# 01_MPPT_controller.net
KiCad netlist of a schematic drawn in Altium Designer
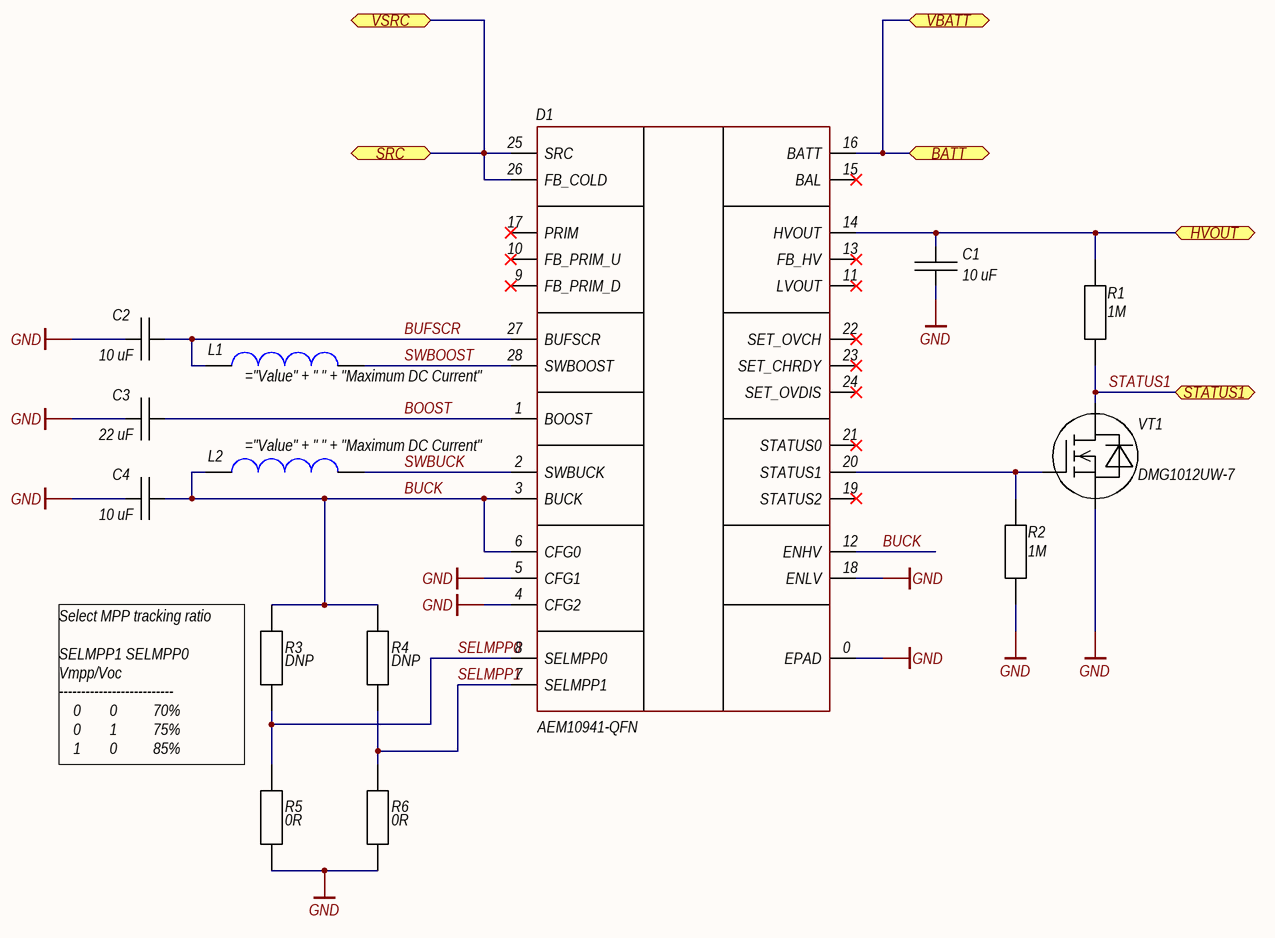
[diagram p0: 01_MPPT_controller.SchDoc]

(export (version "E")
  (design (tool "Eeschema 10.0.6"))
  (components
    (comp (ref "C1")
      (value "10 uF")
      (footprint "CAPC1608X09N")
      (description "Ceramic capacitor")
      (fields
        (field (name "MANUFACTURER") "Murata Electronics")
        (field (name "PARTNUMBER") "GRM188R61A106ME69D")
      )
      (libsource (lib "Node01") (part "Ceramic"))
    )
    (comp (ref "C2")
      (value "10 uF")
      (footprint "CAPC1608X09N")
      (description "Ceramic capacitor")
      (fields
        (field (name "MANUFACTURER") "Murata Electronics")
        (field (name "PARTNUMBER") "GRM188R61A106ME69D")
      )
      (libsource (lib "Node01") (part "Ceramic"))
    )
    (comp (ref "C3")
      (value "22 uF")
      (footprint "CAPC1608X09N")
      (description "Ceramic capacitor")
      (fields
        (field (name "MANUFACTURER") "Murata Electronics")
        (field (name "PARTNUMBER") "GRM188R61A226ME15D")
      )
      (libsource (lib "Node01") (part "Ceramic"))
    )
    (comp (ref "C4")
      (value "10 uF")
      (footprint "CAPC1608X09N")
      (description "Ceramic capacitor")
      (fields
        (field (name "MANUFACTURER") "Murata Electronics")
        (field (name "PARTNUMBER") "GRM188R61A106ME69D")
      )
      (libsource (lib "Node01") (part "Ceramic"))
    )
    (comp (ref "D1")
      (value "~")
      (footprint "QFN50P500X500X85_HS-29N")
      (fields (field (name "MANUFACTURER") "e-peas") (field (name "PARTNUMBER") "AEM10941-QFN"))
      (libsource (lib "Node01") (part "AEM10941-QFN28"))
    )
    (comp (ref "L1")
      (value "10 uH750 mA")
      (footprint "INDP3939X11N")
      (description "Inductor")
      (fields (field (name "MANUFACTURER") "Coilcraft") (field (name "PARTNUMBER") "LPS4012-103MRB"))
      (libsource (lib "Node01") (part "Inductor"))
    )
    (comp (ref "L2")
      (value "10 uH250 mA")
      (footprint "INDC1608X08N")
      (description "Inductor")
      (fields (field (name "MANUFACTURER") "TDK") (field (name "PARTNUMBER") "MLZ1608M100WT000"))
      (libsource (lib "Node01") (part "Inductor"))
    )
    (comp (ref "R1")
      (value "1M")
      (footprint "RESC1608X05N")
      (description "SMD resistor")
      (fields (field (name "MANUFACTURER") "Yageo") (field (name "PARTNUMBER") "RC0603JR-071ML"))
      (libsource (lib "Node01") (part "resistor_smd"))
    )
    (comp (ref "R2")
      (value "1M")
      (footprint "RESC1608X05N")
      (description "SMD resistor")
      (fields (field (name "MANUFACTURER") "Yageo") (field (name "PARTNUMBER") "RC0603JR-071ML"))
      (libsource (lib "Node01") (part "resistor_smd"))
    )
    (comp (ref "R3")
      (value "DNP")
      (footprint "RESC1608X05N")
      (description "SMD resistor")
      (fields (field (name "MANUFACTURER") "Yageo") (field (name "PARTNUMBER") "AC0603FR-070RL"))
      (libsource (lib "Node01") (part "resistor_smd"))
    )
    (comp (ref "R4")
      (value "DNP")
      (footprint "RESC1608X05N")
      (description "SMD resistor")
      (fields (field (name "MANUFACTURER") "Yageo") (field (name "PARTNUMBER") "AC0603FR-070RL"))
      (libsource (lib "Node01") (part "resistor_smd"))
    )
    (comp (ref "R5")
      (value "0R")
      (footprint "RESC1608X05N")
      (description "SMD resistor")
      (fields (field (name "MANUFACTURER") "Yageo") (field (name "PARTNUMBER") "AC0603FR-070RL"))
      (libsource (lib "Node01") (part "resistor_smd"))
    )
    (comp (ref "R6")
      (value "0R")
      (footprint "RESC1608X05N")
      (description "SMD resistor")
      (fields (field (name "MANUFACTURER") "Yageo") (field (name "PARTNUMBER") "AC0603FR-070RL"))
      (libsource (lib "Node01") (part "resistor_smd"))
    )
    (comp (ref "VT1")
      (value "DMG1012UW-7")
      (footprint "SOT65P210X110-3N")
      (description "MOSFET DMG1012UW , N-channel, 20V, 1A")
      (fields (field (name "MANUFACTURER") "Diodes Incorporated"))
      (libsource (lib "Node01") (part "DMF1012UW N-channel MOSFET"))
    )
  )
  (nets
    (net (code "1") (name "/BATT") (class "Default")
      (node (ref "D1") (pin "16") (pinfunction "BATT_16") (pintype "power_in"))
    )
    (net (code "2") (name "/BOOST") (class "Default")
      (node (ref "C3") (pin "2") (pintype "power_in"))
      (node (ref "D1") (pin "1") (pinfunction "BOOST_1") (pintype "power_in"))
    )
    (net (code "3") (name "/BUCK") (class "Default")
      (node (ref "C4") (pin "2") (pintype "power_in"))
      (node (ref "D1") (pin "12") (pinfunction "ENHV_12") (pintype "power_in"))
      (node (ref "D1") (pin "3") (pinfunction "BUCK_3") (pintype "power_in"))
      (node (ref "D1") (pin "6") (pinfunction "CFG0_6") (pintype "power_in"))
      (node (ref "L2") (pin "1") (pinfunction "1_1") (pintype "power_in"))
      (node (ref "R3") (pin "2") (pinfunction "2_2") (pintype "power_in"))
      (node (ref "R4") (pin "2") (pinfunction "2_2") (pintype "power_in"))
    )
    (net (code "4") (name "/BUFSCR") (class "Default")
      (node (ref "C2") (pin "2") (pintype "power_in"))
      (node (ref "D1") (pin "27") (pinfunction "BUFSCR_27") (pintype "power_in"))
      (node (ref "L1") (pin "1") (pinfunction "1_1") (pintype "power_in"))
    )
    (net (code "5") (name "/HVOUT") (class "Default")
      (node (ref "C1") (pin "2") (pintype "power_in"))
      (node (ref "D1") (pin "14") (pinfunction "HVOUT_14") (pintype "power_in"))
      (node (ref "R1") (pin "1") (pinfunction "1_1") (pintype "power_in"))
    )
    (net (code "6") (name "/SELMPP0") (class "Default")
      (node (ref "D1") (pin "8") (pinfunction "SELMPP0_8") (pintype "power_in"))
      (node (ref "R3") (pin "1") (pinfunction "1_1") (pintype "power_in"))
      (node (ref "R5") (pin "2") (pinfunction "2_2") (pintype "power_in"))
    )
    (net (code "7") (name "/SELMPP1") (class "Default")
      (node (ref "D1") (pin "7") (pinfunction "SELMPP1_7") (pintype "power_in"))
      (node (ref "R4") (pin "1") (pinfunction "1_1") (pintype "power_in"))
      (node (ref "R6") (pin "2") (pinfunction "2_2") (pintype "power_in"))
    )
    (net (code "8") (name "/SRC") (class "Default")
      (node (ref "D1") (pin "25") (pinfunction "SRC_25") (pintype "power_in"))
      (node (ref "D1") (pin "26") (pinfunction "FB_COLD_26") (pintype "power_in"))
    )
    (net (code "9") (name "/STATUS1") (class "Default")
      (node (ref "R1") (pin "2") (pinfunction "2_2") (pintype "power_in"))
      (node (ref "VT1") (pin "3") (pinfunction "D_3") (pintype "power_in"))
    )
    (net (code "10") (name "/SWBOOST") (class "Default")
      (node (ref "D1") (pin "28") (pinfunction "SWBOOST_28") (pintype "power_in"))
      (node (ref "L1") (pin "2") (pinfunction "2_2") (pintype "power_in"))
    )
    (net (code "11") (name "/SWBUCK") (class "Default")
      (node (ref "D1") (pin "2") (pinfunction "SWBUCK_2") (pintype "power_in"))
      (node (ref "L2") (pin "2") (pinfunction "2_2") (pintype "power_in"))
    )
    (net (code "12") (name "GND") (class "Default")
      (node (ref "C1") (pin "1") (pintype "power_in"))
      (node (ref "C2") (pin "1") (pintype "power_in"))
      (node (ref "C3") (pin "1") (pintype "power_in"))
      (node (ref "C4") (pin "1") (pintype "power_in"))
      (node (ref "D1") (pin "0") (pinfunction "EPAD_0") (pintype "power_in"))
      (node (ref "D1") (pin "18") (pinfunction "ENLV_18") (pintype "power_in"))
      (node (ref "D1") (pin "4") (pinfunction "CFG2_4") (pintype "power_in"))
      (node (ref "D1") (pin "5") (pinfunction "CFG1_5") (pintype "power_in"))
      (node (ref "R2") (pin "2") (pinfunction "2_2") (pintype "power_in"))
      (node (ref "R5") (pin "1") (pinfunction "1_1") (pintype "power_in"))
      (node (ref "R6") (pin "1") (pinfunction "1_1") (pintype "power_in"))
      (node (ref "VT1") (pin "2") (pinfunction "S_2") (pintype "power_in"))
    )
    (net (code "13") (name "Net-(D1-STATUS1)") (class "Default")
      (node (ref "D1") (pin "20") (pinfunction "STATUS1_20") (pintype "power_in"))
      (node (ref "R2") (pin "1") (pinfunction "1_1") (pintype "power_in"))
      (node (ref "VT1") (pin "1") (pinfunction "G_1") (pintype "power_in"))
    )
    (net (code "14") (name "unconnected-(D1-BAL-Pad15)") (class "Default")
      (node (ref "D1") (pin "15") (pinfunction "BAL_15") (pintype "power_in+no_connect"))
    )
    (net (code "15") (name "unconnected-(D1-FB_HV-Pad13)") (class "Default")
      (node (ref "D1") (pin "13") (pinfunction "FB_HV_13") (pintype "power_in+no_connect"))
    )
    (net (code "16") (name "unconnected-(D1-FB_PRIM_D-Pad9)") (class "Default")
      (node (ref "D1") (pin "9") (pinfunction "FB_PRIM_D_9") (pintype "power_in+no_connect"))
    )
    (net (code "17") (name "unconnected-(D1-FB_PRIM_U-Pad10)") (class "Default")
      (node (ref "D1") (pin "10") (pinfunction "FB_PRIM_U_10") (pintype "power_in+no_connect"))
    )
    (net (code "18") (name "unconnected-(D1-LVOUT-Pad11)") (class "Default")
      (node (ref "D1") (pin "11") (pinfunction "LVOUT_11") (pintype "power_in+no_connect"))
    )
    (net (code "19") (name "unconnected-(D1-PRIM-Pad17)") (class "Default")
      (node (ref "D1") (pin "17") (pinfunction "PRIM_17") (pintype "power_in+no_connect"))
    )
    (net (code "20") (name "unconnected-(D1-SET_CHRDY-Pad23)") (class "Default")
      (node (ref "D1") (pin "23") (pinfunction "SET_CHRDY_23") (pintype "power_in+no_connect"))
    )
    (net (code "21") (name "unconnected-(D1-SET_OVCH-Pad22)") (class "Default")
      (node (ref "D1") (pin "22") (pinfunction "SET_OVCH_22") (pintype "power_in+no_connect"))
    )
    (net (code "22") (name "unconnected-(D1-SET_OVDIS-Pad24)") (class "Default")
      (node (ref "D1") (pin "24") (pinfunction "SET_OVDIS_24") (pintype "power_in+no_connect"))
    )
    (net (code "23") (name "unconnected-(D1-STATUS0-Pad21)") (class "Default")
      (node (ref "D1") (pin "21") (pinfunction "STATUS0_21") (pintype "power_in+no_connect"))
    )
    (net (code "24") (name "unconnected-(D1-STATUS2-Pad19)") (class "Default")
      (node (ref "D1") (pin "19") (pinfunction "STATUS2_19") (pintype "power_in+no_connect"))
    )
  )
)
